# ktirBase.net
KiCad netlist of a schematic drawn in EAGLE
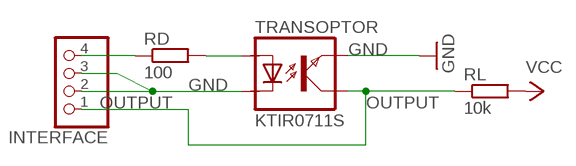
[diagram p0: schematic, sheet 1]

(export (version "E")
  (design (tool "Eeschema 10.0.6"))
  (components
    (comp (ref "INTERFACE")
      (value "PINHD-1X4/90")
      (footprint "eagle-import:1X04_90")
      (libsource (lib "eagle-import") (part "PINHD-1X4/90"))
    )
    (comp (ref "RD")
      (value "100")
      (footprint "eagle-import:0204_7")
      (libsource (lib "eagle-import") (part "R-EU_0204/7"))
    )
    (comp (ref "RL")
      (value "10k")
      (footprint "eagle-import:0204_7")
      (libsource (lib "eagle-import") (part "R-EU_0204/7"))
    )
    (comp (ref "TRANSOPTOR")
      (value "KTIR0711S")
      (footprint "eagle-import:TOP")
      (libsource (lib "eagle-import") (part "KTIR0711S"))
    )
  )
  (nets
    (net (code "1") (name "/OUTPUT") (class "Default")
      (node (ref "INTERFACE") (pin "1") (pinfunction "1_1") (pintype "passive"))
      (node (ref "RL") (pin "1") (pinfunction "1_1") (pintype "passive"))
      (node (ref "TRANSOPTOR") (pin "KOLEKTOR") (pinfunction "KOLEKTOR_KOLEKTOR") (pintype "bidirectional"))
    )
    (net (code "2") (name "GND") (class "Default")
      (node (ref "INTERFACE") (pin "2") (pinfunction "2_2") (pintype "passive"))
      (node (ref "INTERFACE") (pin "3") (pinfunction "3_3") (pintype "passive"))
      (node (ref "TRANSOPTOR") (pin "EMITER") (pinfunction "EMITER_EMITER") (pintype "bidirectional"))
      (node (ref "TRANSOPTOR") (pin "KATODA") (pinfunction "KATODA_KATODA") (pintype "passive"))
    )
    (net (code "3") (name "Net-(RD-Pad2)") (class "Default")
      (node (ref "RD") (pin "2") (pinfunction "2_2") (pintype "passive"))
      (node (ref "TRANSOPTOR") (pin "ANODA") (pinfunction "ANODA_ANODA") (pintype "passive"))
    )
    (net (code "4") (name "VCC") (class "Default")
      (node (ref "INTERFACE") (pin "4") (pinfunction "4_4") (pintype "passive"))
      (node (ref "RD") (pin "1") (pinfunction "1_1") (pintype "passive"))
      (node (ref "RL") (pin "2") (pinfunction "2_2") (pintype "passive"))
    )
  )
)
